# Capteur.net
KiCad netlist of a schematic drawn in Altium Designer
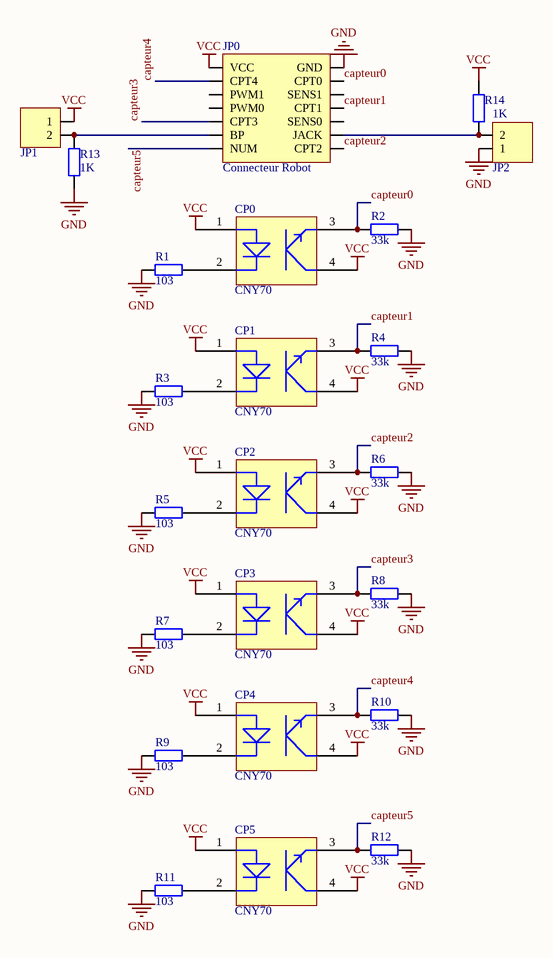
[diagram p0: Capteur.SchDoc]

(export (version "E")
  (design (tool "Eeschema 10.0.6"))
  (components
    (comp (ref "CP0")
      (value "CNY70")
      (footprint "CNY70")
      (description "Reflective optical sensor")
      (fields (field (name "MANUFACTURER") "VISHAY SILICONIX"))
      (libsource (lib "GEII1") (part "CNY70"))
    )
    (comp (ref "CP1")
      (value "CNY70")
      (footprint "CNY70")
      (description "Reflective optical sensor")
      (fields (field (name "MANUFACTURER") "VISHAY SILICONIX"))
      (libsource (lib "GEII1") (part "CNY70"))
    )
    (comp (ref "CP2")
      (value "CNY70")
      (footprint "CNY70")
      (description "Reflective optical sensor")
      (fields (field (name "MANUFACTURER") "VISHAY SILICONIX"))
      (libsource (lib "GEII1") (part "CNY70"))
    )
    (comp (ref "CP3")
      (value "CNY70")
      (footprint "CNY70")
      (description "Reflective optical sensor")
      (fields (field (name "MANUFACTURER") "VISHAY SILICONIX"))
      (libsource (lib "GEII1") (part "CNY70"))
    )
    (comp (ref "CP4")
      (value "CNY70")
      (footprint "CNY70")
      (description "Reflective optical sensor")
      (fields (field (name "MANUFACTURER") "VISHAY SILICONIX"))
      (libsource (lib "GEII1") (part "CNY70"))
    )
    (comp (ref "CP5")
      (value "CNY70")
      (footprint "CNY70")
      (description "Reflective optical sensor")
      (fields (field (name "MANUFACTURER") "VISHAY SILICONIX"))
      (libsource (lib "GEII1") (part "CNY70"))
    )
    (comp (ref "JP0")
      (value "Connecteur Robot")
      (footprint "HE10 2x7")
      (description "Connecteurr pour robot S1")
      (libsource (lib "GEII1") (part "HE10 Robot"))
    )
    (comp (ref "JP1")
      (value "Connecteur bipastille")
      (footprint "Conn_SIG_2pts")
      (description "Double pastilles pour souder un moteur")
      (libsource (lib "GEII1") (part "Connecteur bipastille"))
    )
    (comp (ref "JP2")
      (value "Connecteur bipastille")
      (footprint "Conn_SIG_2pts")
      (description "Double pastilles pour souder un moteur")
      (libsource (lib "") (part "Connecteur bipastille_1"))
    )
    (comp (ref "R1")
      (value "103")
      (footprint "Axial_4")
      (description "Resistance")
      (fields (field (name "PUBLISHER") "Altium Limited"))
      (libsource (lib "GEII1") (part "Res"))
    )
    (comp (ref "R2")
      (value "33k")
      (footprint "Axial_4")
      (description "Resistance")
      (fields (field (name "PUBLISHER") "Altium Limited"))
      (libsource (lib "GEII1") (part "Res"))
    )
    (comp (ref "R3")
      (value "103")
      (footprint "Axial_4")
      (description "Resistance")
      (fields (field (name "PUBLISHER") "Altium Limited"))
      (libsource (lib "GEII1") (part "Res"))
    )
    (comp (ref "R4")
      (value "33k")
      (footprint "Axial_4")
      (description "Resistance")
      (fields (field (name "PUBLISHER") "Altium Limited"))
      (libsource (lib "GEII1") (part "Res"))
    )
    (comp (ref "R5")
      (value "103")
      (footprint "Axial_4")
      (description "Resistance")
      (fields (field (name "PUBLISHER") "Altium Limited"))
      (libsource (lib "GEII1") (part "Res"))
    )
    (comp (ref "R6")
      (value "33k")
      (footprint "Axial_4")
      (description "Resistance")
      (fields (field (name "PUBLISHER") "Altium Limited"))
      (libsource (lib "GEII1") (part "Res"))
    )
    (comp (ref "R7")
      (value "103")
      (footprint "Axial_4")
      (description "Resistance")
      (fields (field (name "PUBLISHER") "Altium Limited"))
      (libsource (lib "GEII1") (part "Res"))
    )
    (comp (ref "R8")
      (value "33k")
      (footprint "Axial_4")
      (description "Resistance")
      (fields (field (name "PUBLISHER") "Altium Limited"))
      (libsource (lib "GEII1") (part "Res"))
    )
    (comp (ref "R9")
      (value "103")
      (footprint "Axial_4")
      (description "Resistance")
      (fields (field (name "PUBLISHER") "Altium Limited"))
      (libsource (lib "GEII1") (part "Res"))
    )
    (comp (ref "R10")
      (value "33k")
      (footprint "Axial_4")
      (description "Resistance")
      (fields (field (name "PUBLISHER") "Altium Limited"))
      (libsource (lib "GEII1") (part "Res"))
    )
    (comp (ref "R11")
      (value "103")
      (footprint "Axial_4")
      (description "Resistance")
      (fields (field (name "PUBLISHER") "Altium Limited"))
      (libsource (lib "GEII1") (part "Res"))
    )
    (comp (ref "R12")
      (value "33k")
      (footprint "Axial_4")
      (description "Resistance")
      (fields (field (name "PUBLISHER") "Altium Limited"))
      (libsource (lib "GEII1") (part "Res"))
    )
    (comp (ref "R13")
      (value "1K")
      (footprint "Axial_4")
      (description "Resistance")
      (fields (field (name "PUBLISHER") "Altium Limited"))
      (libsource (lib "") (part "Res_1"))
    )
    (comp (ref "R14")
      (value "1K")
      (footprint "Axial_4")
      (description "Resistance")
      (fields (field (name "PUBLISHER") "Altium Limited"))
      (libsource (lib "") (part "Res_1"))
    )
  )
  (nets
    (net (code "1") (name "/capteur0") (class "Default")
      (node (ref "CP0") (pin "3") (pinfunction "E_3") (pintype "passive"))
      (node (ref "JP0") (pin "4") (pinfunction "CPT0_4") (pintype "passive"))
      (node (ref "R2") (pin "1") (pinfunction "1_1") (pintype "passive"))
    )
    (net (code "2") (name "/capteur1") (class "Default")
      (node (ref "CP1") (pin "3") (pinfunction "E_3") (pintype "passive"))
      (node (ref "JP0") (pin "8") (pinfunction "CPT1_8") (pintype "passive"))
      (node (ref "R4") (pin "1") (pinfunction "1_1") (pintype "passive"))
    )
    (net (code "3") (name "/capteur2") (class "Default")
      (node (ref "CP2") (pin "3") (pinfunction "E_3") (pintype "passive"))
      (node (ref "JP0") (pin "14") (pinfunction "CPT2_14") (pintype "passive"))
      (node (ref "R6") (pin "1") (pinfunction "1_1") (pintype "passive"))
    )
    (net (code "4") (name "/capteur3") (class "Default")
      (node (ref "CP3") (pin "3") (pinfunction "E_3") (pintype "passive"))
      (node (ref "JP0") (pin "9") (pinfunction "CPT3_9") (pintype "passive"))
      (node (ref "R8") (pin "1") (pinfunction "1_1") (pintype "passive"))
    )
    (net (code "5") (name "/capteur4") (class "Default")
      (node (ref "CP4") (pin "3") (pinfunction "E_3") (pintype "passive"))
      (node (ref "JP0") (pin "3") (pinfunction "CPT4_3") (pintype "passive"))
      (node (ref "R10") (pin "1") (pinfunction "1_1") (pintype "passive"))
    )
    (net (code "6") (name "/capteur5") (class "Default")
      (node (ref "CP5") (pin "3") (pinfunction "E_3") (pintype "passive"))
      (node (ref "JP0") (pin "13") (pinfunction "NUM_13") (pintype "passive"))
      (node (ref "R12") (pin "1") (pinfunction "1_1") (pintype "passive"))
    )
    (net (code "7") (name "GND") (class "Default")
      (node (ref "JP0") (pin "2") (pinfunction "GND_2") (pintype "passive"))
      (node (ref "JP2") (pin "1") (pinfunction "1_1") (pintype "passive"))
      (node (ref "R1") (pin "1") (pinfunction "1_1") (pintype "passive"))
      (node (ref "R10") (pin "2") (pinfunction "2_2") (pintype "passive"))
      (node (ref "R11") (pin "1") (pinfunction "1_1") (pintype "passive"))
      (node (ref "R12") (pin "2") (pinfunction "2_2") (pintype "passive"))
      (node (ref "R13") (pin "1") (pinfunction "1_1") (pintype "passive"))
      (node (ref "R2") (pin "2") (pinfunction "2_2") (pintype "passive"))
      (node (ref "R3") (pin "1") (pinfunction "1_1") (pintype "passive"))
      (node (ref "R4") (pin "2") (pinfunction "2_2") (pintype "passive"))
      (node (ref "R5") (pin "1") (pinfunction "1_1") (pintype "passive"))
      (node (ref "R6") (pin "2") (pinfunction "2_2") (pintype "passive"))
      (node (ref "R7") (pin "1") (pinfunction "1_1") (pintype "passive"))
      (node (ref "R8") (pin "2") (pinfunction "2_2") (pintype "passive"))
      (node (ref "R9") (pin "1") (pinfunction "1_1") (pintype "passive"))
    )
    (net (code "8") (name "Net-(CP0-K)") (class "Default")
      (node (ref "CP0") (pin "2") (pinfunction "K_2") (pintype "passive"))
      (node (ref "R1") (pin "2") (pinfunction "2_2") (pintype "passive"))
    )
    (net (code "9") (name "Net-(CP1-K)") (class "Default")
      (node (ref "CP1") (pin "2") (pinfunction "K_2") (pintype "passive"))
      (node (ref "R3") (pin "2") (pinfunction "2_2") (pintype "passive"))
    )
    (net (code "10") (name "Net-(CP2-K)") (class "Default")
      (node (ref "CP2") (pin "2") (pinfunction "K_2") (pintype "passive"))
      (node (ref "R5") (pin "2") (pinfunction "2_2") (pintype "passive"))
    )
    (net (code "11") (name "Net-(CP3-K)") (class "Default")
      (node (ref "CP3") (pin "2") (pinfunction "K_2") (pintype "passive"))
      (node (ref "R7") (pin "2") (pinfunction "2_2") (pintype "passive"))
    )
    (net (code "12") (name "Net-(CP4-K)") (class "Default")
      (node (ref "CP4") (pin "2") (pinfunction "K_2") (pintype "passive"))
      (node (ref "R9") (pin "2") (pinfunction "2_2") (pintype "passive"))
    )
    (net (code "13") (name "Net-(CP5-K)") (class "Default")
      (node (ref "CP5") (pin "2") (pinfunction "K_2") (pintype "passive"))
      (node (ref "R11") (pin "2") (pinfunction "2_2") (pintype "passive"))
    )
    (net (code "14") (name "Net-(JP0-BP)") (class "Default")
      (node (ref "JP0") (pin "11") (pinfunction "BP_11") (pintype "passive"))
      (node (ref "JP1") (pin "2") (pinfunction "2_2") (pintype "passive"))
      (node (ref "R13") (pin "2") (pinfunction "2_2") (pintype "passive"))
    )
    (net (code "15") (name "Net-(JP0-JACK)") (class "Default")
      (node (ref "JP0") (pin "12") (pinfunction "JACK_12") (pintype "passive"))
      (node (ref "JP2") (pin "2") (pinfunction "2_2") (pintype "passive"))
      (node (ref "R14") (pin "1") (pinfunction "1_1") (pintype "passive"))
    )
    (net (code "16") (name "VCC") (class "Default")
      (node (ref "CP0") (pin "1") (pinfunction "A_1") (pintype "passive"))
      (node (ref "CP0") (pin "4") (pinfunction "C_4") (pintype "passive"))
      (node (ref "CP1") (pin "1") (pinfunction "A_1") (pintype "passive"))
      (node (ref "CP1") (pin "4") (pinfunction "C_4") (pintype "passive"))
      (node (ref "CP2") (pin "1") (pinfunction "A_1") (pintype "passive"))
      (node (ref "CP2") (pin "4") (pinfunction "C_4") (pintype "passive"))
      (node (ref "CP3") (pin "1") (pinfunction "A_1") (pintype "passive"))
      (node (ref "CP3") (pin "4") (pinfunction "C_4") (pintype "passive"))
      (node (ref "CP4") (pin "1") (pinfunction "A_1") (pintype "passive"))
      (node (ref "CP4") (pin "4") (pinfunction "C_4") (pintype "passive"))
      (node (ref "CP5") (pin "1") (pinfunction "A_1") (pintype "passive"))
      (node (ref "CP5") (pin "4") (pinfunction "C_4") (pintype "passive"))
      (node (ref "JP0") (pin "1") (pinfunction "VCC_1") (pintype "passive"))
      (node (ref "JP1") (pin "1") (pinfunction "1_1") (pintype "passive"))
      (node (ref "R14") (pin "2") (pinfunction "2_2") (pintype "passive"))
    )
    (net (code "17") (name "unconnected-(JP0-PWM0-Pad7)") (class "Default")
      (node (ref "JP0") (pin "7") (pinfunction "PWM0_7") (pintype "passive"))
    )
    (net (code "18") (name "unconnected-(JP0-PWM1-Pad5)") (class "Default")
      (node (ref "JP0") (pin "5") (pinfunction "PWM1_5") (pintype "passive"))
    )
    (net (code "19") (name "unconnected-(JP0-SENS0-Pad10)") (class "Default")
      (node (ref "JP0") (pin "10") (pinfunction "SENS0_10") (pintype "passive"))
    )
    (net (code "20") (name "unconnected-(JP0-SENS1-Pad6)") (class "Default")
      (node (ref "JP0") (pin "6") (pinfunction "SENS1_6") (pintype "passive"))
    )
  )
)
